# EVENTCTRL_FPGA.net
KiCad netlist of a schematic drawn in Altium Designer
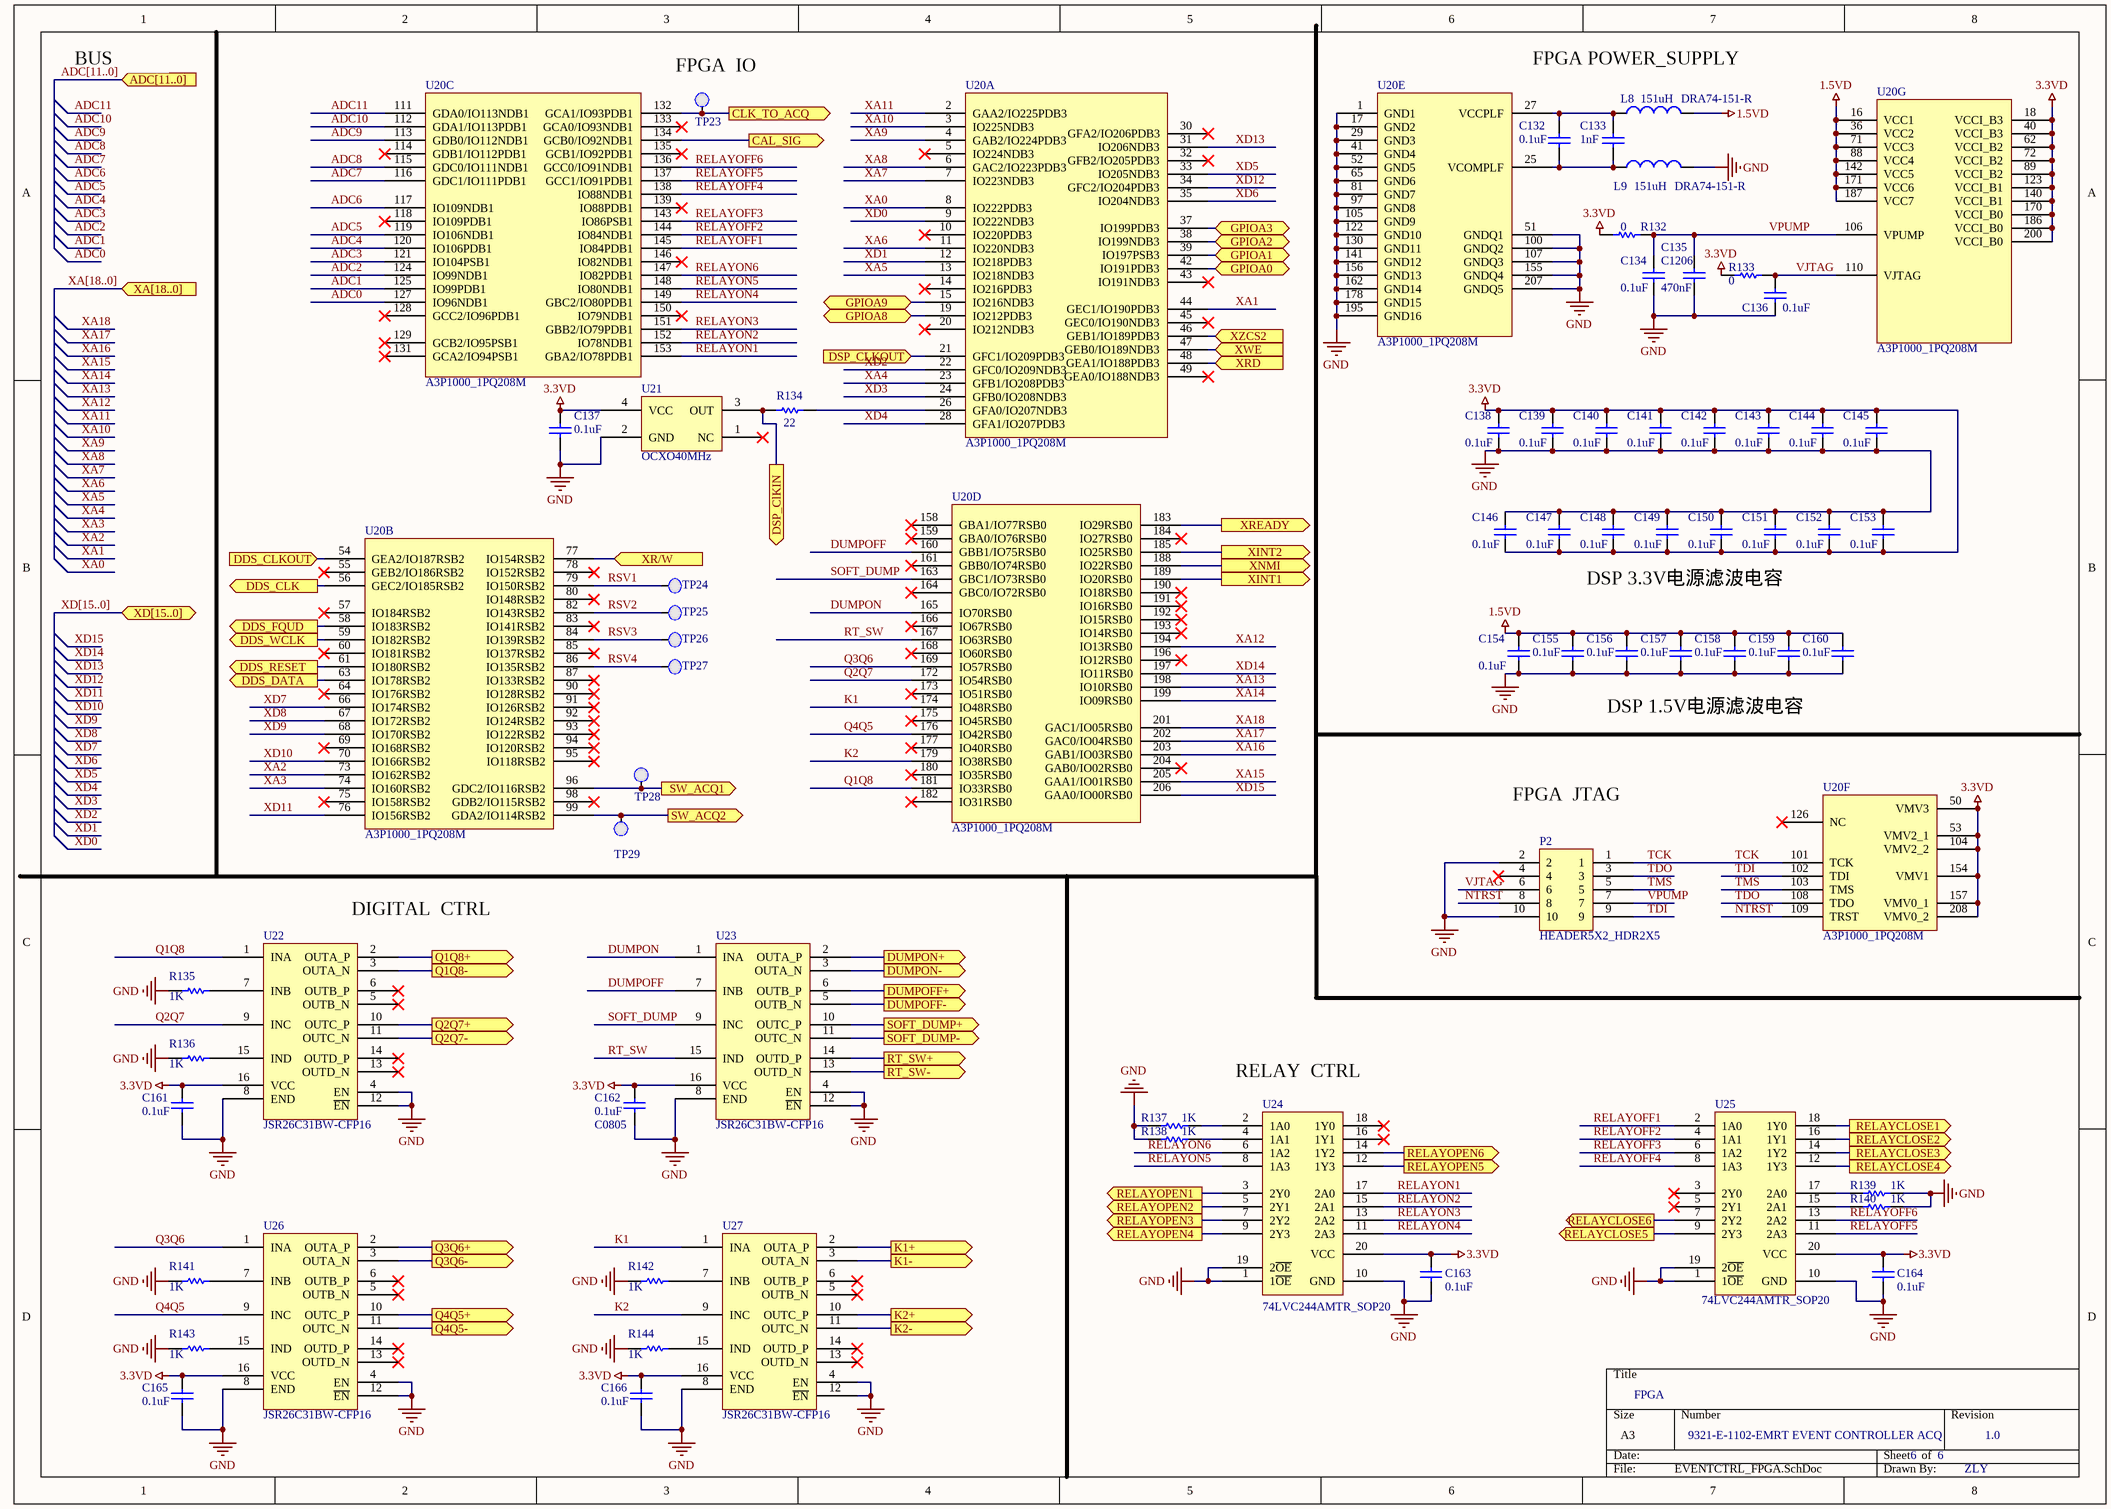
[diagram p0: EVENTCTRL_FPGA.SchDoc]

(export (version "E")
  (design (tool "Eeschema 10.0.6"))
  (components
    (comp (ref "C132")
      (value "0.1uF")
      (footprint "0805")
      (description "Capacitor")
      (fields (field (name "Comment") "C0805"))
      (libsource (lib "Miscellaneous Devices") (part "Cap"))
    )
    (comp (ref "C133")
      (value "1nF")
      (footprint "0805")
      (description "Capacitor")
      (fields (field (name "Comment") "C0805"))
      (libsource (lib "Miscellaneous Devices") (part "Cap"))
    )
    (comp (ref "C134")
      (value "0.1uF")
      (footprint "0805")
      (description "Capacitor")
      (fields (field (name "Comment") "C0805"))
      (libsource (lib "Miscellaneous Devices") (part "Cap"))
    )
    (comp (ref "C135")
      (value "C1206")
      (footprint "1206")
      (description "Capacitor")
      (fields (field (name "ALTIUM_VALUE") "470nF"))
      (libsource (lib "Miscellaneous Devices") (part "Cap"))
    )
    (comp (ref "C136")
      (value "0.1uF")
      (footprint "0805")
      (description "Capacitor")
      (fields (field (name "Comment") "C0805"))
      (libsource (lib "Miscellaneous Devices") (part "Cap"))
    )
    (comp (ref "C137")
      (value "0.1uF")
      (footprint "0805")
      (description "Capacitor")
      (fields (field (name "Comment") "C0805"))
      (libsource (lib "Miscellaneous Devices") (part "Cap"))
    )
    (comp (ref "C138")
      (value "0.1uF")
      (footprint "0805")
      (description "Capacitor")
      (fields (field (name "Comment") "C0805"))
      (libsource (lib "Miscellaneous Devices") (part "Cap"))
    )
    (comp (ref "C139")
      (value "0.1uF")
      (footprint "0805")
      (description "Capacitor")
      (fields (field (name "Comment") "C0805"))
      (libsource (lib "Miscellaneous Devices") (part "Cap"))
    )
    (comp (ref "C140")
      (value "0.1uF")
      (footprint "0805")
      (description "Capacitor")
      (fields (field (name "Comment") "C0805"))
      (libsource (lib "Miscellaneous Devices") (part "Cap"))
    )
    (comp (ref "C141")
      (value "0.1uF")
      (footprint "0805")
      (description "Capacitor")
      (fields (field (name "Comment") "C0805"))
      (libsource (lib "Miscellaneous Devices") (part "Cap"))
    )
    (comp (ref "C142")
      (value "0.1uF")
      (footprint "0805")
      (description "Capacitor")
      (fields (field (name "Comment") "C0805"))
      (libsource (lib "Miscellaneous Devices") (part "Cap"))
    )
    (comp (ref "C143")
      (value "0.1uF")
      (footprint "0805")
      (description "Capacitor")
      (fields (field (name "Comment") "C0805"))
      (libsource (lib "Miscellaneous Devices") (part "Cap"))
    )
    (comp (ref "C144")
      (value "0.1uF")
      (footprint "0805")
      (description "Capacitor")
      (fields (field (name "Comment") "C0805"))
      (libsource (lib "Miscellaneous Devices") (part "Cap"))
    )
    (comp (ref "C145")
      (value "0.1uF")
      (footprint "0805")
      (description "Capacitor")
      (fields (field (name "Comment") "C0805"))
      (libsource (lib "Miscellaneous Devices") (part "Cap"))
    )
    (comp (ref "C146")
      (value "0.1uF")
      (footprint "0805")
      (description "Capacitor")
      (fields (field (name "Comment") "C0805"))
      (libsource (lib "Miscellaneous Devices") (part "Cap"))
    )
    (comp (ref "C147")
      (value "0.1uF")
      (footprint "0805")
      (description "Capacitor")
      (fields (field (name "Comment") "C0805"))
      (libsource (lib "Miscellaneous Devices") (part "Cap"))
    )
    (comp (ref "C148")
      (value "0.1uF")
      (footprint "0805")
      (description "Capacitor")
      (fields (field (name "Comment") "C0805"))
      (libsource (lib "Miscellaneous Devices") (part "Cap"))
    )
    (comp (ref "C149")
      (value "0.1uF")
      (footprint "0805")
      (description "Capacitor")
      (fields (field (name "Comment") "C0805"))
      (libsource (lib "Miscellaneous Devices") (part "Cap"))
    )
    (comp (ref "C150")
      (value "0.1uF")
      (footprint "0805")
      (description "Capacitor")
      (fields (field (name "Comment") "C0805"))
      (libsource (lib "Miscellaneous Devices") (part "Cap"))
    )
    (comp (ref "C151")
      (value "0.1uF")
      (footprint "0805")
      (description "Capacitor")
      (fields (field (name "Comment") "C0805"))
      (libsource (lib "Miscellaneous Devices") (part "Cap"))
    )
    (comp (ref "C152")
      (value "0.1uF")
      (footprint "0805")
      (description "Capacitor")
      (fields (field (name "Comment") "C0805"))
      (libsource (lib "Miscellaneous Devices") (part "Cap"))
    )
    (comp (ref "C153")
      (value "0.1uF")
      (footprint "0805")
      (description "Capacitor")
      (fields (field (name "Comment") "C0805"))
      (libsource (lib "Miscellaneous Devices") (part "Cap"))
    )
    (comp (ref "C154")
      (value "0.1uF")
      (footprint "0805")
      (description "Capacitor")
      (fields (field (name "Comment") "C0805"))
      (libsource (lib "Miscellaneous Devices") (part "Cap"))
    )
    (comp (ref "C155")
      (value "0.1uF")
      (footprint "0805")
      (description "Capacitor")
      (fields (field (name "Comment") "C0805"))
      (libsource (lib "Miscellaneous Devices") (part "Cap"))
    )
    (comp (ref "C156")
      (value "0.1uF")
      (footprint "0805")
      (description "Capacitor")
      (fields (field (name "Comment") "C0805"))
      (libsource (lib "Miscellaneous Devices") (part "Cap"))
    )
    (comp (ref "C157")
      (value "0.1uF")
      (footprint "0805")
      (description "Capacitor")
      (fields (field (name "Comment") "C0805"))
      (libsource (lib "Miscellaneous Devices") (part "Cap"))
    )
    (comp (ref "C158")
      (value "0.1uF")
      (footprint "0805")
      (description "Capacitor")
      (fields (field (name "Comment") "C0805"))
      (libsource (lib "Miscellaneous Devices") (part "Cap"))
    )
    (comp (ref "C159")
      (value "0.1uF")
      (footprint "0805")
      (description "Capacitor")
      (fields (field (name "Comment") "C0805"))
      (libsource (lib "Miscellaneous Devices") (part "Cap"))
    )
    (comp (ref "C160")
      (value "0.1uF")
      (footprint "0805")
      (description "Capacitor")
      (fields (field (name "Comment") "C0805"))
      (libsource (lib "Miscellaneous Devices") (part "Cap"))
    )
    (comp (ref "C161")
      (value "0.1uF")
      (footprint "0805")
      (description "Capacitor")
      (fields (field (name "Comment") "C0805"))
      (libsource (lib "Miscellaneous Devices") (part "Cap"))
    )
    (comp (ref "C162")
      (value "0.1uF")
      (footprint "0805")
      (description "Capacitor")
      (fields (field (name "PACKAGEREFERENCE") "C0805") (field (name "Comment") "C0805"))
      (libsource (lib "Miscellaneous Devices") (part "Cap"))
    )
    (comp (ref "C163")
      (value "0.1uF")
      (footprint "0805")
      (description "Capacitor")
      (fields (field (name "Comment") "C0805"))
      (libsource (lib "Miscellaneous Devices") (part "Cap"))
    )
    (comp (ref "C164")
      (value "0.1uF")
      (footprint "0805")
      (description "Capacitor")
      (fields (field (name "Comment") "C0805"))
      (libsource (lib "Miscellaneous Devices") (part "Cap"))
    )
    (comp (ref "C165")
      (value "0.1uF")
      (footprint "0805")
      (description "Capacitor")
      (fields (field (name "Comment") "C0805"))
      (libsource (lib "Miscellaneous Devices") (part "Cap"))
    )
    (comp (ref "C166")
      (value "0.1uF")
      (footprint "0805")
      (description "Capacitor")
      (fields (field (name "Comment") "C0805"))
      (libsource (lib "Miscellaneous Devices") (part "Cap"))
    )
    (comp (ref "L8")
      (value "DRA74-151-R")
      (footprint "DRA74-151-R")
      (description "Inductor")
      (fields (field (name "ALTIUM_VALUE") "151uH"))
      (libsource (lib "Miscellaneous Devices") (part "Inductor"))
    )
    (comp (ref "L9")
      (value "DRA74-151-R")
      (footprint "DRA74-151-R")
      (description "Inductor")
      (fields (field (name "ALTIUM_VALUE") "151uH"))
      (libsource (lib "Miscellaneous Devices") (part "Inductor"))
    )
    (comp (ref "P2")
      (value "HEADER5X2_HDR2X5")
      (footprint "HDR2X5")
      (libsource (lib "srj") (part "JTAG_PORT10"))
    )
    (comp (ref "R132")
      (value "0")
      (footprint "R0805")
      (description "Resistor")
      (fields (field (name "Comment") "R0805"))
      (libsource (lib "Miscellaneous Devices") (part "Res1"))
    )
    (comp (ref "R133")
      (value "0")
      (footprint "R0805")
      (description "Resistor")
      (fields (field (name "Comment") "R0805"))
      (libsource (lib "Miscellaneous Devices") (part "Res1"))
    )
    (comp (ref "R134")
      (value "22")
      (footprint "R0805")
      (description "Resistor")
      (fields (field (name "Comment") "R0805"))
      (libsource (lib "Miscellaneous Devices") (part "Res1"))
    )
    (comp (ref "R135")
      (value "1K")
      (footprint "R0805")
      (description "Resistor")
      (fields (field (name "Comment") "R0805"))
      (libsource (lib "Miscellaneous Devices") (part "Res1"))
    )
    (comp (ref "R136")
      (value "1K")
      (footprint "R0805")
      (description "Resistor")
      (fields (field (name "Comment") "R0805"))
      (libsource (lib "Miscellaneous Devices") (part "Res1"))
    )
    (comp (ref "R137")
      (value "1K")
      (footprint "R0805")
      (description "Resistor")
      (fields (field (name "Comment") "R0805"))
      (libsource (lib "Miscellaneous Devices") (part "Res1"))
    )
    (comp (ref "R138")
      (value "1K")
      (footprint "R0805")
      (description "Resistor")
      (fields (field (name "Comment") "R0805"))
      (libsource (lib "Miscellaneous Devices") (part "Res1"))
    )
    (comp (ref "R139")
      (value "1K")
      (footprint "R0805")
      (description "Resistor")
      (fields (field (name "Comment") "R0805"))
      (libsource (lib "Miscellaneous Devices") (part "Res1"))
    )
    (comp (ref "R140")
      (value "1K")
      (footprint "R0805")
      (description "Resistor")
      (fields (field (name "Comment") "R0805"))
      (libsource (lib "Miscellaneous Devices") (part "Res1"))
    )
    (comp (ref "R141")
      (value "1K")
      (footprint "R0805")
      (description "Resistor")
      (fields (field (name "Comment") "R0805"))
      (libsource (lib "Miscellaneous Devices") (part "Res1"))
    )
    (comp (ref "R142")
      (value "1K")
      (footprint "R0805")
      (description "Resistor")
      (fields (field (name "Comment") "R0805"))
      (libsource (lib "Miscellaneous Devices") (part "Res1"))
    )
    (comp (ref "R143")
      (value "1K")
      (footprint "R0805")
      (description "Resistor")
      (fields (field (name "Comment") "R0805"))
      (libsource (lib "Miscellaneous Devices") (part "Res1"))
    )
    (comp (ref "R144")
      (value "1K")
      (footprint "R0805")
      (description "Resistor")
      (fields (field (name "Comment") "R0805"))
      (libsource (lib "Miscellaneous Devices") (part "Res1"))
    )
    (comp (ref "TP23") (value "TP") (footprint "TPA") (libsource (lib "") (part "TP_2")))
    (comp (ref "TP24") (value "TP") (footprint "TPA") (libsource (lib "*") (part "TP")))
    (comp (ref "TP25") (value "TP") (footprint "TPA") (libsource (lib "*") (part "TP")))
    (comp (ref "TP26") (value "TP") (footprint "TPA") (libsource (lib "*") (part "TP")))
    (comp (ref "TP27") (value "TP") (footprint "TPA") (libsource (lib "*") (part "TP")))
    (comp (ref "TP28") (value "TP") (footprint "TPA") (libsource (lib "") (part "TP_2")))
    (comp (ref "TP29") (value "TP") (footprint "TPA") (libsource (lib "") (part "TP_1")))
    (comp (ref "U20")
      (value "A3P1000_1PQ208M")
      (footprint "PQFP208")
      (libsource (lib "srj") (part "A3P1000"))
    )
    (comp (ref "U21") (value "OCXO40MHz") (footprint "OCX1") (libsource (lib "srj") (part "OCXO")))
    (comp (ref "U22") (value "JSR26C31BW-CFP16") (footprint "W16A") (libsource (lib "srj") (part "JSR26C31")))
    (comp (ref "U23") (value "JSR26C31BW-CFP16") (footprint "W16A") (libsource (lib "srj") (part "JSR26C31")))
    (comp (ref "U24")
      (value "74LVC244AMTR_SOP20")
      (footprint "EVENTCTRL:SOP20")
      (libsource (lib "srj") (part "74HC244"))
    )
    (comp (ref "U25")
      (value "74LVC244AMTR_SOP20")
      (footprint "EVENTCTRL:SOP20")
      (libsource (lib "srj") (part "74HC244"))
    )
    (comp (ref "U26") (value "JSR26C31BW-CFP16") (footprint "W16A") (libsource (lib "srj") (part "JSR26C31")))
    (comp (ref "U27") (value "JSR26C31BW-CFP16") (footprint "W16A") (libsource (lib "srj") (part "JSR26C31")))
  )
  (nets
    (net (code "1") (name "/ADC0") (class "Default")
      (node (ref "U20") (pin "127") (pinfunction "IO96NDB1_127") (pintype "passive"))
    )
    (net (code "2") (name "/ADC1") (class "Default")
      (node (ref "U20") (pin "125") (pinfunction "IO99PDB1_125") (pintype "passive"))
    )
    (net (code "3") (name "/ADC2") (class "Default")
      (node (ref "U20") (pin "124") (pinfunction "IO99NDB1_124") (pintype "passive"))
    )
    (net (code "4") (name "/ADC3") (class "Default")
      (node (ref "U20") (pin "121") (pinfunction "IO104PSB1_121") (pintype "passive"))
    )
    (net (code "5") (name "/ADC4") (class "Default")
      (node (ref "U20") (pin "120") (pinfunction "IO106PDB1_120") (pintype "passive"))
    )
    (net (code "6") (name "/ADC5") (class "Default")
      (node (ref "U20") (pin "119") (pinfunction "IO106NDB1_119") (pintype "passive"))
    )
    (net (code "7") (name "/ADC6") (class "Default")
      (node (ref "U20") (pin "117") (pinfunction "IO109NDB1_117") (pintype "passive"))
    )
    (net (code "8") (name "/ADC7") (class "Default")
      (node (ref "U20") (pin "116") (pinfunction "GDC1/IO111PDB1_116") (pintype "passive"))
    )
    (net (code "9") (name "/ADC8") (class "Default")
      (node (ref "U20") (pin "115") (pinfunction "GDC0/IO111NDB1_115") (pintype "passive"))
    )
    (net (code "10") (name "/ADC9") (class "Default")
      (node (ref "U20") (pin "113") (pinfunction "GDB0/IO112NDB1_113") (pintype "passive"))
    )
    (net (code "11") (name "/ADC10") (class "Default")
      (node (ref "U20") (pin "112") (pinfunction "GDA1/IO113PDB1_112") (pintype "passive"))
    )
    (net (code "12") (name "/ADC11") (class "Default")
      (node (ref "U20") (pin "111") (pinfunction "GDA0/IO113NDB1_111") (pintype "passive"))
    )
    (net (code "14") (name "/CAL_SIG") (class "Default")
      (node (ref "U20") (pin "134") (pinfunction "GCB0/IO92NDB1_134") (pintype "passive"))
    )
    (net (code "15") (name "/CLK_TO_ACQ") (class "Default")
      (node (ref "TP23") (pin "1") (pinfunction "TP_1") (pintype "passive"))
      (node (ref "U20") (pin "132") (pinfunction "GCA1/IO93PDB1_132") (pintype "passive"))
    )
    (net (code "16") (name "/DDS_CLK") (class "Default")
      (node (ref "U20") (pin "56") (pinfunction "GEC2/IO185RSB2_56") (pintype "passive"))
    )
    (net (code "17") (name "/DDS_CLKOUT") (class "Default")
      (node (ref "U20") (pin "54") (pinfunction "GEA2/IO187RSB2_54") (pintype "passive"))
    )
    (net (code "18") (name "/DDS_DATA") (class "Default")
      (node (ref "U20") (pin "63") (pinfunction "IO178RSB2_63") (pintype "passive"))
    )
    (net (code "19") (name "/DDS_FQUD") (class "Default")
      (node (ref "U20") (pin "58") (pinfunction "IO183RSB2_58") (pintype "passive"))
    )
    (net (code "20") (name "/DDS_RESET") (class "Default")
      (node (ref "U20") (pin "61") (pinfunction "IO180RSB2_61") (pintype "passive"))
    )
    (net (code "21") (name "/DDS_WCLK") (class "Default")
      (node (ref "U20") (pin "59") (pinfunction "IO182RSB2_59") (pintype "passive"))
    )
    (net (code "22") (name "/DSP_CLKOUT") (class "Default")
      (node (ref "U20") (pin "21") (pinfunction "GFC1/IO209PDB3_21") (pintype "passive"))
    )
    (net (code "23") (name "/DSP_ClKIN") (class "Default")
      (node (ref "R134") (pin "1") (pinfunction "1_1") (pintype "passive"))
      (node (ref "U21") (pin "3") (pinfunction "OUT_3") (pintype "passive"))
    )
    (net (code "24") (name "/DUMPOFF") (class "Default")
      (node (ref "U20") (pin "160") (pinfunction "GBB1/IO75RSB0_160") (pintype "passive"))
      (node (ref "U23") (pin "7") (pinfunction "INB_7") (pintype "passive"))
    )
    (net (code "25") (name "/DUMPOFF+") (class "Default")
      (node (ref "U23") (pin "6") (pinfunction "OUTB_P_6") (pintype "passive"))
    )
    (net (code "26") (name "/DUMPOFF-") (class "Default")
      (node (ref "U23") (pin "5") (pinfunction "OUTB_N_5") (pintype "passive"))
    )
    (net (code "27") (name "/DUMPON") (class "Default")
      (node (ref "U20") (pin "165") (pinfunction "IO70RSB0_165") (pintype "passive"))
      (node (ref "U23") (pin "1") (pinfunction "INA_1") (pintype "passive"))
    )
    (net (code "28") (name "/DUMPON+") (class "Default")
      (node (ref "U23") (pin "2") (pinfunction "OUTA_P_2") (pintype "passive"))
    )
    (net (code "29") (name "/DUMPON-") (class "Default")
      (node (ref "U23") (pin "3") (pinfunction "OUTA_N_3") (pintype "passive"))
    )
    (net (code "30") (name "/GPIOA0") (class "Default")
      (node (ref "U20") (pin "42") (pinfunction "IO191PDB3_42") (pintype "passive"))
    )
    (net (code "31") (name "/GPIOA1") (class "Default")
      (node (ref "U20") (pin "39") (pinfunction "IO197PSB3_39") (pintype "passive"))
    )
    (net (code "32") (name "/GPIOA2") (class "Default")
      (node (ref "U20") (pin "38") (pinfunction "IO199NDB3_38") (pintype "passive"))
    )
    (net (code "33") (name "/GPIOA3") (class "Default")
      (node (ref "U20") (pin "37") (pinfunction "IO199PDB3_37") (pintype "passive"))
    )
    (net (code "34") (name "/GPIOA8") (class "Default")
      (node (ref "U20") (pin "19") (pinfunction "IO212PDB3_19") (pintype "passive"))
    )
    (net (code "35") (name "/GPIOA9") (class "Default")
      (node (ref "U20") (pin "15") (pinfunction "IO216NDB3_15") (pintype "passive"))
    )
    (net (code "36") (name "/K1") (class "Default")
      (node (ref "U20") (pin "174") (pinfunction "IO48RSB0_174") (pintype "passive"))
      (node (ref "U27") (pin "1") (pinfunction "INA_1") (pintype "passive"))
    )
    (net (code "37") (name "/K1+") (class "Default")
      (node (ref "U27") (pin "2") (pinfunction "OUTA_P_2") (pintype "passive"))
    )
    (net (code "38") (name "/K1-") (class "Default")
      (node (ref "U27") (pin "3") (pinfunction "OUTA_N_3") (pintype "passive"))
    )
    (net (code "39") (name "/K2") (class "Default")
      (node (ref "U20") (pin "179") (pinfunction "IO38RSB0_179") (pintype "passive"))
      (node (ref "U27") (pin "9") (pinfunction "INC_9") (pintype "passive"))
    )
    (net (code "40") (name "/K2+") (class "Default")
      (node (ref "U27") (pin "10") (pinfunction "OUTC_P_10") (pintype "passive"))
    )
    (net (code "41") (name "/K2-") (class "Default")
      (node (ref "U27") (pin "11") (pinfunction "OUTC_N_11") (pintype "passive"))
    )
    (net (code "42") (name "/NTRST") (class "Default")
      (node (ref "P2") (pin "8") (pinfunction "8_8") (pintype "passive"))
      (node (ref "U20") (pin "109") (pinfunction "TRST_109") (pintype "passive"))
    )
    (net (code "43") (name "/Q1Q8") (class "Default")
      (node (ref "U20") (pin "181") (pinfunction "IO33RSB0_181") (pintype "passive"))
      (node (ref "U22") (pin "1") (pinfunction "INA_1") (pintype "passive"))
    )
    (net (code "44") (name "/Q1Q8+") (class "Default")
      (node (ref "U22") (pin "2") (pinfunction "OUTA_P_2") (pintype "passive"))
    )
    (net (code "45") (name "/Q1Q8-") (class "Default")
      (node (ref "U22") (pin "3") (pinfunction "OUTA_N_3") (pintype "passive"))
    )
    (net (code "46") (name "/Q2Q7") (class "Default")
      (node (ref "U20") (pin "172") (pinfunction "IO54RSB0_172") (pintype "passive"))
      (node (ref "U22") (pin "9") (pinfunction "INC_9") (pintype "passive"))
    )
    (net (code "47") (name "/Q2Q7+") (class "Default")
      (node (ref "U22") (pin "10") (pinfunction "OUTC_P_10") (pintype "passive"))
    )
    (net (code "48") (name "/Q2Q7-") (class "Default")
      (node (ref "U22") (pin "11") (pinfunction "OUTC_N_11") (pintype "passive"))
    )
    (net (code "49") (name "/Q3Q6") (class "Default")
      (node (ref "U20") (pin "169") (pinfunction "IO57RSB0_169") (pintype "passive"))
      (node (ref "U26") (pin "1") (pinfunction "INA_1") (pintype "passive"))
    )
    (net (code "50") (name "/Q3Q6+") (class "Default")
      (node (ref "U26") (pin "2") (pinfunction "OUTA_P_2") (pintype "passive"))
    )
    (net (code "51") (name "/Q3Q6-") (class "Default")
      (node (ref "U26") (pin "3") (pinfunction "OUTA_N_3") (pintype "passive"))
    )
    (net (code "52") (name "/Q4Q5") (class "Default")
      (node (ref "U20") (pin "176") (pinfunction "IO42RSB0_176") (pintype "passive"))
      (node (ref "U26") (pin "9") (pinfunction "INC_9") (pintype "passive"))
    )
    (net (code "53") (name "/Q4Q5+") (class "Default")
      (node (ref "U26") (pin "10") (pinfunction "OUTC_P_10") (pintype "passive"))
    )
    (net (code "54") (name "/Q4Q5-") (class "Default")
      (node (ref "U26") (pin "11") (pinfunction "OUTC_N_11") (pintype "passive"))
    )
    (net (code "55") (name "/RELAYCLOSE1") (class "Default")
      (node (ref "U25") (pin "18") (pinfunction "1Y0_18") (pintype "passive"))
    )
    (net (code "56") (name "/RELAYCLOSE2") (class "Default")
      (node (ref "U25") (pin "16") (pinfunction "1Y1_16") (pintype "passive"))
    )
    (net (code "57") (name "/RELAYCLOSE3") (class "Default")
      (node (ref "U25") (pin "14") (pinfunction "1Y2_14") (pintype "passive"))
    )
    (net (code "58") (name "/RELAYCLOSE4") (class "Default")
      (node (ref "U25") (pin "12") (pinfunction "1Y3_12") (pintype "passive"))
    )
    (net (code "59") (name "/RELAYCLOSE5") (class "Default")
      (node (ref "U25") (pin "9") (pinfunction "2Y3_9") (pintype "passive"))
    )
    (net (code "60") (name "/RELAYCLOSE6") (class "Default")
      (node (ref "U25") (pin "7") (pinfunction "2Y2_7") (pintype "passive"))
    )
    (net (code "61") (name "/RELAYOFF1") (class "Default")
      (node (ref "U20") (pin "145") (pinfunction "IO84PDB1_145") (pintype "passive"))
      (node (ref "U25") (pin "2") (pinfunction "1A0_2") (pintype "passive"))
    )
    (net (code "62") (name "/RELAYOFF2") (class "Default")
      (node (ref "U20") (pin "144") (pinfunction "IO84NDB1_144") (pintype "passive"))
      (node (ref "U25") (pin "4") (pinfunction "1A1_4") (pintype "passive"))
    )
    (net (code "63") (name "/RELAYOFF3") (class "Default")
      (node (ref "U20") (pin "143") (pinfunction "IO86PSB1_143") (pintype "passive"))
      (node (ref "U25") (pin "6") (pinfunction "1A2_6") (pintype "passive"))
    )
    (net (code "64") (name "/RELAYOFF4") (class "Default")
      (node (ref "U20") (pin "138") (pinfunction "IO88NDB1_138") (pintype "passive"))
      (node (ref "U25") (pin "8") (pinfunction "1A3_8") (pintype "passive"))
    )
    (net (code "65") (name "/RELAYOFF5") (class "Default")
      (node (ref "U20") (pin "137") (pinfunction "GCC1/IO91PDB1_137") (pintype "passive"))
      (node (ref "U25") (pin "11") (pinfunction "2A3_11") (pintype "passive"))
    )
    (net (code "66") (name "/RELAYOFF6") (class "Default")
      (node (ref "U20") (pin "136") (pinfunction "GCC0/IO91NDB1_136") (pintype "passive"))
      (node (ref "U25") (pin "13") (pinfunction "2A2_13") (pintype "passive"))
    )
    (net (code "67") (name "/RELAYON1") (class "Default")
      (node (ref "U20") (pin "153") (pinfunction "GBA2/IO78PDB1_153") (pintype "passive"))
      (node (ref "U24") (pin "17") (pinfunction "2A0_17") (pintype "passive"))
    )
    (net (code "68") (name "/RELAYON2") (class "Default")
      (node (ref "U20") (pin "152") (pinfunction "IO78NDB1_152") (pintype "passive"))
      (node (ref "U24") (pin "15") (pinfunction "2A1_15") (pintype "passive"))
    )
    (net (code "69") (name "/RELAYON3") (class "Default")
      (node (ref "U20") (pin "151") (pinfunction "GBB2/IO79PDB1_151") (pintype "passive"))
      (node (ref "U24") (pin "13") (pinfunction "2A2_13") (pintype "passive"))
    )
    (net (code "70") (name "/RELAYON4") (class "Default")
      (node (ref "U20") (pin "149") (pinfunction "GBC2/IO80PDB1_149") (pintype "passive"))
      (node (ref "U24") (pin "11") (pinfunction "2A3_11") (pintype "passive"))
    )
    (net (code "71") (name "/RELAYON5") (class "Default")
      (node (ref "U20") (pin "148") (pinfunction "IO80NDB1_148") (pintype "passive"))
      (node (ref "U24") (pin "8") (pinfunction "1A3_8") (pintype "passive"))
    )
    (net (code "72") (name "/RELAYON6") (class "Default")
      (node (ref "U20") (pin "147") (pinfunction "IO82PDB1_147") (pintype "passive"))
      (node (ref "U24") (pin "6") (pinfunction "1A2_6") (pintype "passive"))
    )
    (net (code "73") (name "/RELAYOPEN1") (class "Default")
      (node (ref "U24") (pin "3") (pinfunction "2Y0_3") (pintype "passive"))
    )
    (net (code "74") (name "/RELAYOPEN2") (class "Default")
      (node (ref "U24") (pin "5") (pinfunction "2Y1_5") (pintype "passive"))
    )
    (net (code "75") (name "/RELAYOPEN3") (class "Default")
      (node (ref "U24") (pin "7") (pinfunction "2Y2_7") (pintype "passive"))
    )
    (net (code "76") (name "/RELAYOPEN4") (class "Default")
      (node (ref "U24") (pin "9") (pinfunction "2Y3_9") (pintype "passive"))
    )
    (net (code "77") (name "/RELAYOPEN5") (class "Default")
      (node (ref "U24") (pin "12") (pinfunction "1Y3_12") (pintype "passive"))
    )
    (net (code "78") (name "/RELAYOPEN6") (class "Default")
      (node (ref "U24") (pin "14") (pinfunction "1Y2_14") (pintype "passive"))
    )
    (net (code "79") (name "/RSV1") (class "Default")
      (node (ref "TP24") (pin "1") (pinfunction "TP_1") (pintype "passive"))
      (node (ref "U20") (pin "79") (pinfunction "IO150RSB2_79") (pintype "passive"))
    )
    (net (code "80") (name "/RSV2") (class "Default")
      (node (ref "TP25") (pin "1") (pinfunction "TP_1") (pintype "passive"))
      (node (ref "U20") (pin "82") (pinfunction "IO143RSB2_82") (pintype "passive"))
    )
    (net (code "81") (name "/RSV3") (class "Default")
      (node (ref "TP26") (pin "1") (pinfunction "TP_1") (pintype "passive"))
      (node (ref "U20") (pin "84") (pinfunction "IO139RSB2_84") (pintype "passive"))
    )
    (net (code "82") (name "/RSV4") (class "Default")
      (node (ref "TP27") (pin "1") (pinfunction "TP_1") (pintype "passive"))
      (node (ref "U20") (pin "86") (pinfunction "IO135RSB2_86") (pintype "passive"))
    )
    (net (code "83") (name "/RT_SW") (class "Default")
      (node (ref "U20") (pin "167") (pinfunction "IO63RSB0_167") (pintype "passive"))
      (node (ref "U23") (pin "15") (pinfunction "IND_15") (pintype "passive"))
    )
    (net (code "84") (name "/RT_SW+") (class "Default")
      (node (ref "U23") (pin "14") (pinfunction "OUTD_P_14") (pintype "passive"))
    )
    (net (code "85") (name "/RT_SW-") (class "Default")
      (node (ref "U23") (pin "13") (pinfunction "OUTD_N_13") (pintype "passive"))
    )
    (net (code "86") (name "/SOFT_DUMP") (class "Default")
      (node (ref "U20") (pin "163") (pinfunction "GBC1/IO73RSB0_163") (pintype "passive"))
      (node (ref "U23") (pin "9") (pinfunction "INC_9") (pintype "passive"))
    )
    (net (code "87") (name "/SOFT_DUMP+") (class "Default")
      (node (ref "U23") (pin "10") (pinfunction "OUTC_P_10") (pintype "passive"))
    )
    (net (code "88") (name "/SOFT_DUMP-") (class "Default")
      (node (ref "U23") (pin "11") (pinfunction "OUTC_N_11") (pintype "passive"))
    )
    (net (code "89") (name "/SW_ACQ1") (class "Default")
      (node (ref "TP28") (pin "1") (pinfunction "TP_1") (pintype "passive"))
      (node (ref "U20") (pin "96") (pinfunction "GDC2/IO116RSB2_96") (pintype "passive"))
    )
    (net (code "90") (name "/SW_ACQ2") (class "Default")
      (node (ref "TP29") (pin "1") (pinfunction "TP_1") (pintype "passive"))
      (node (ref "U20") (pin "99") (pinfunction "GDA2/IO114RSB2_99") (pintype "passive"))
    )
    (net (code "91") (name "/TCK") (class "Default")
      (node (ref "P2") (pin "1") (pinfunction "1_1") (pintype "passive"))
      (node (ref "U20") (pin "101") (pinfunction "TCK_101") (pintype "passive"))
    )
    (net (code "92") (name "/TDI") (class "Default")
      (node (ref "P2") (pin "9") (pinfunction "9_9") (pintype "passive"))
      (node (ref "U20") (pin "102") (pinfunction "TDI_102") (pintype "passive"))
    )
    (net (code "93") (name "/TDO") (class "Default")
      (node (ref "P2") (pin "3") (pinfunction "3_3") (pintype "passive"))
      (node (ref "U20") (pin "108") (pinfunction "TDO_108") (pintype "passive"))
    )
    (net (code "94") (name "/TMS") (class "Default")
      (node (ref "P2") (pin "5") (pinfunction "5_5") (pintype "passive"))
      (node (ref "U20") (pin "103") (pinfunction "TMS_103") (pintype "passive"))
    )
    (net (code "95") (name "/VJTAG") (class "Default")
      (node (ref "C136") (pin "1") (pinfunction "1_1") (pintype "passive"))
      (node (ref "P2") (pin "6") (pinfunction "6_6") (pintype "passive"))
      (node (ref "R133") (pin "2") (pinfunction "2_2") (pintype "passive"))
      (node (ref "U20") (pin "110") (pinfunction "VJTAG_110") (pintype "passive"))
    )
    (net (code "96") (name "/VPUMP") (class "Default")
      (node (ref "C134") (pin "1") (pinfunction "1_1") (pintype "passive"))
      (node (ref "C135") (pin "1") (pinfunction "1_1") (pintype "passive"))
      (node (ref "P2") (pin "7") (pinfunction "7_7") (pintype "passive"))
      (node (ref "R132") (pin "2") (pinfunction "2_2") (pintype "passive"))
      (node (ref "U20") (pin "106") (pinfunction "VPUMP_106") (pintype "passive"))
    )
    (net (code "97") (name "/XA0") (class "Default")
      (node (ref "U20") (pin "8") (pinfunction "IO222PDB3_8") (pintype "passive"))
    )
    (net (code "98") (name "/XA1") (class "Default")
      (node (ref "U20") (pin "44") (pinfunction "GEC1/IO190PDB3_44") (pintype "passive"))
    )
    (net (code "99") (name "/XA2") (class "Default")
      (node (ref "U20") (pin "73") (pinfunction "IO162RSB2_73") (pintype "passive"))
    )
    (net (code "100") (name "/XA3") (class "Default")
      (node (ref "U20") (pin "74") (pinfunction "IO160RSB2_74") (pintype "passive"))
    )
    (net (code "101") (name "/XA4") (class "Default")
      (node (ref "U20") (pin "23") (pinfunction "GFB1/IO208PDB3_23") (pintype "passive"))
    )
    (net (code "102") (name "/XA5") (class "Default")
      (node (ref "U20") (pin "13") (pinfunction "IO218NDB3_13") (pintype "passive"))
    )
    (net (code "103") (name "/XA6") (class "Default")
      (node (ref "U20") (pin "11") (pinfunction "IO220NDB3_11") (pintype "passive"))
    )
    (net (code "104") (name "/XA7") (class "Default")
      (node (ref "U20") (pin "7") (pinfunction "IO223NDB3_7") (pintype "passive"))
    )
    (net (code "105") (name "/XA8") (class "Default")
      (node (ref "U20") (pin "6") (pinfunction "GAC2/IO223PDB3_6") (pintype "passive"))
    )
    (net (code "106") (name "/XA9") (class "Default")
      (node (ref "U20") (pin "4") (pinfunction "GAB2/IO224PDB3_4") (pintype "passive"))
    )
    (net (code "107") (name "/XA10") (class "Default")
      (node (ref "U20") (pin "3") (pinfunction "IO225NDB3_3") (pintype "passive"))
    )
    (net (code "108") (name "/XA11") (class "Default")
      (node (ref "U20") (pin "2") (pinfunction "GAA2/IO225PDB3_2") (pintype "passive"))
    )
    (net (code "109") (name "/XA12") (class "Default")
      (node (ref "U20") (pin "194") (pinfunction "IO13RSB0_194") (pintype "passive"))
    )
    (net (code "110") (name "/XA13") (class "Default")
      (node (ref "U20") (pin "198") (pinfunction "IO10RSB0_198") (pintype "passive"))
    )
    (net (code "111") (name "/XA14") (class "Default")
      (node (ref "U20") (pin "199") (pinfunction "IO09RSB0_199") (pintype "passive"))
    )
    (net (code "112") (name "/XA15") (class "Default")
      (node (ref "U20") (pin "205") (pinfunction "GAA1/IO01RSB0_205") (pintype "passive"))
    )
    (net (code "113") (name "/XA16") (class "Default")
      (node (ref "U20") (pin "203") (pinfunction "GAB1/IO03RSB0_203") (pintype "passive"))
    )
    (net (code "114") (name "/XA17") (class "Default")
      (node (ref "U20") (pin "202") (pinfunction "GAC0/IO04RSB0_202") (pintype "passive"))
    )
    (net (code "115") (name "/XA18") (class "Default")
      (node (ref "U20") (pin "201") (pinfunction "GAC1/IO05RSB0_201") (pintype "passive"))
    )
    (net (code "117") (name "/XD0") (class "Default")
      (node (ref "U20") (pin "9") (pinfunction "IO222NDB3_9") (pintype "passive"))
    )
    (net (code "118") (name "/XD1") (class "Default")
      (node (ref "U20") (pin "12") (pinfunction "IO218PDB3_12") (pintype "passive"))
    )
    (net (code "119") (name "/XD2") (class "Default")
      (node (ref "U20") (pin "22") (pinfunction "GFC0/IO209NDB3_22") (pintype "passive"))
    )
    (net (code "120") (name "/XD3") (class "Default")
      (node (ref "U20") (pin "24") (pinfunction "GFB0/IO208NDB3_24") (pintype "passive"))
    )
    (net (code "121") (name "/XD4") (class "Default")
      (node (ref "U20") (pin "28") (pinfunction "GFA1/IO207PDB3_28") (pintype "passive"))
    )
    (net (code "122") (name "/XD5") (class "Default")
      (node (ref "U20") (pin "33") (pinfunction "IO205NDB3_33") (pintype "passive"))
    )
    (net (code "123") (name "/XD6") (class "Default")
      (node (ref "U20") (pin "35") (pinfunction "IO204NDB3_35") (pintype "passive"))
    )
    (net (code "124") (name "/XD7") (class "Default")
      (node (ref "U20") (pin "66") (pinfunction "IO174RSB2_66") (pintype "passive"))
    )
    (net (code "125") (name "/XD8") (class "Default")
      (node (ref "U20") (pin "67") (pinfunction "IO172RSB2_67") (pintype "passive"))
    )
    (net (code "126") (name "/XD9") (class "Default")
      (node (ref "U20") (pin "68") (pinfunction "IO170RSB2_68") (pintype "passive"))
    )
    (net (code "127") (name "/XD10") (class "Default")
      (node (ref "U20") (pin "70") (pinfunction "IO166RSB2_70") (pintype "passive"))
    )
    (net (code "128") (name "/XD11") (class "Default")
      (node (ref "U20") (pin "76") (pinfunction "IO156RSB2_76") (pintype "passive"))
    )
    (net (code "129") (name "/XD12") (class "Default")
      (node (ref "U20") (pin "34") (pinfunction "GFC2/IO204PDB3_34") (pintype "passive"))
    )
    (net (code "130") (name "/XD13") (class "Default")
      (node (ref "U20") (pin "31") (pinfunction "IO206NDB3_31") (pintype "passive"))
    )
    (net (code "131") (name "/XD14") (class "Default")
      (node (ref "U20") (pin "197") (pinfunction "IO11RSB0_197") (pintype "passive"))
    )
    (net (code "132") (name "/XD15") (class "Default")
      (node (ref "U20") (pin "206") (pinfunction "GAA0/IO00RSB0_206") (pintype "passive"))
    )
    (net (code "134") (name "/XINT1") (class "Default")
      (node (ref "U20") (pin "189") (pinfunction "IO20RSB0_189") (pintype "passive"))
    )
    (net (code "135") (name "/XINT2") (class "Default")
      (node (ref "U20") (pin "185") (pinfunction "IO25RSB0_185") (pintype "passive"))
    )
    (net (code "136") (name "/XNMI") (class "Default")
      (node (ref "U20") (pin "188") (pinfunction "IO22RSB0_188") (pintype "passive"))
    )
    (net (code "137") (name "/XRD") (class "Default")
      (node (ref "U20") (pin "48") (pinfunction "GEA1/IO188PDB3_48") (pintype "passive"))
    )
    (net (code "138") (name "/XREADY") (class "Default")
      (node (ref "U20") (pin "183") (pinfunction "IO29RSB0_183") (pintype "passive"))
    )
    (net (code "139") (name "/XR{slash}W") (class "Default")
      (node (ref "U20") (pin "77") (pinfunction "IO154RSB2_77") (pintype "passive"))
    )
    (net (code "140") (name "/XWE") (class "Default")
      (node (ref "U20") (pin "47") (pinfunction "GEB0/IO189NDB3_47") (pintype "passive"))
    )
    (net (code "141") (name "/XZCS2") (class "Default")
      (node (ref "U20") (pin "46") (pinfunction "GEB1/IO189PDB3_46") (pintype "passive"))
    )
    (net (code "142") (name "1.5VD") (class "Default")
      (node (ref "C154") (pin "1") (pinfunction "1_1") (pintype "passive"))
      (node (ref "C155") (pin "1") (pinfunction "1_1") (pintype "passive"))
      (node (ref "C156") (pin "1") (pinfunction "1_1") (pintype "passive"))
      (node (ref "C157") (pin "1") (pinfunction "1_1") (pintype "passive"))
      (node (ref "C158") (pin "1") (pinfunction "1_1") (pintype "passive"))
      (node (ref "C159") (pin "1") (pinfunction "1_1") (pintype "passive"))
      (node (ref "C160") (pin "1") (pinfunction "1_1") (pintype "passive"))
      (node (ref "L8") (pin "2") (pinfunction "2_2") (pintype "passive"))
      (node (ref "U20") (pin "142") (pinfunction "VCC5_142") (pintype "passive"))
      (node (ref "U20") (pin "16") (pinfunction "VCC1_16") (pintype "passive"))
      (node (ref "U20") (pin "171") (pinfunction "VCC6_171") (pintype "passive"))
      (node (ref "U20") (pin "187") (pinfunction "VCC7_187") (pintype "passive"))
      (node (ref "U20") (pin "36") (pinfunction "VCC2_36") (pintype "passive"))
      (node (ref "U20") (pin "71") (pinfunction "VCC3_71") (pintype "passive"))
      (node (ref "U20") (pin "88") (pinfunction "VCC4_88") (pintype "passive"))
    )
    (net (code "143") (name "3.3VD") (class "Default")
      (node (ref "C137") (pin "1") (pinfunction "1_1") (pintype "passive"))
      (node (ref "C138") (pin "1") (pinfunction "1_1") (pintype "passive"))
      (node (ref "C139") (pin "1") (pinfunction "1_1") (pintype "passive"))
      (node (ref "C140") (pin "1") (pinfunction "1_1") (pintype "passive"))
      (node (ref "C141") (pin "1") (pinfunction "1_1") (pintype "passive"))
      (node (ref "C142") (pin "1") (pinfunction "1_1") (pintype "passive"))
      (node (ref "C143") (pin "1") (pinfunction "1_1") (pintype "passive"))
      (node (ref "C144") (pin "1") (pinfunction "1_1") (pintype "passive"))
      (node (ref "C145") (pin "1") (pinfunction "1_1") (pintype "passive"))
      (node (ref "C146") (pin "2") (pinfunction "2_2") (pintype "passive"))
      (node (ref "C147") (pin "2") (pinfunction "2_2") (pintype "passive"))
      (node (ref "C148") (pin "2") (pinfunction "2_2") (pintype "passive"))
      (node (ref "C149") (pin "2") (pinfunction "2_2") (pintype "passive"))
      (node (ref "C150") (pin "2") (pinfunction "2_2") (pintype "passive"))
      (node (ref "C151") (pin "2") (pinfunction "2_2") (pintype "passive"))
      (node (ref "C152") (pin "2") (pinfunction "2_2") (pintype "passive"))
      (node (ref "C153") (pin "2") (pinfunction "2_2") (pintype "passive"))
      (node (ref "C161") (pin "1") (pinfunction "1_1") (pintype "passive"))
      (node (ref "C162") (pin "1") (pinfunction "1_1") (pintype "passive"))
      (node (ref "C163") (pin "2") (pinfunction "2_2") (pintype "passive"))
      (node (ref "C164") (pin "2") (pinfunction "2_2") (pintype "passive"))
      (node (ref "C165") (pin "1") (pinfunction "1_1") (pintype "passive"))
      (node (ref "C166") (pin "1") (pinfunction "1_1") (pintype "passive"))
      (node (ref "R132") (pin "1") (pinfunction "1_1") (pintype "passive"))
      (node (ref "R133") (pin "1") (pinfunction "1_1") (pintype "passive"))
      (node (ref "U20") (pin "104") (pinfunction "VMV2_2_104") (pintype "passive"))
      (node (ref "U20") (pin "123") (pinfunction "VCCI_B1_123") (pintype "passive"))
      (node (ref "U20") (pin "140") (pinfunction "VCCI_B1_140") (pintype "passive"))
      (node (ref "U20") (pin "154") (pinfunction "VMV1_154") (pintype "passive"))
      (node (ref "U20") (pin "157") (pinfunction "VMV0_1_157") (pintype "passive"))
      (node (ref "U20") (pin "170") (pinfunction "VCCI_B0_170") (pintype "passive"))
      (node (ref "U20") (pin "18") (pinfunction "VCCI_B3_18") (pintype "passive"))
      (node (ref "U20") (pin "186") (pinfunction "VCCI_B0_186") (pintype "passive"))
      (node (ref "U20") (pin "200") (pinfunction "VCCI_B0_200") (pintype "passive"))
      (node (ref "U20") (pin "208") (pinfunction "VMV0_2_208") (pintype "passive"))
      (node (ref "U20") (pin "40") (pinfunction "VCCI_B3_40") (pintype "passive"))
      (node (ref "U20") (pin "50") (pinfunction "VMV3_50") (pintype "passive"))
      (node (ref "U20") (pin "53") (pinfunction "VMV2_1_53") (pintype "passive"))
      (node (ref "U20") (pin "62") (pinfunction "VCCI_B2_62") (pintype "passive"))
      (node (ref "U20") (pin "72") (pinfunction "VCCI_B2_72") (pintype "passive"))
      (node (ref "U20") (pin "89") (pinfunction "VCCI_B2_89") (pintype "passive"))
      (node (ref "U21") (pin "4") (pinfunction "VCC_4") (pintype "passive"))
      (node (ref "U22") (pin "16") (pinfunction "VCC_16") (pintype "passive"))
      (node (ref "U23") (pin "16") (pinfunction "VCC_16") (pintype "passive"))
      (node (ref "U24") (pin "20") (pinfunction "VCC_20") (pintype "passive"))
      (node (ref "U25") (pin "20") (pinfunction "VCC_20") (pintype "passive"))
      (node (ref "U26") (pin "16") (pinfunction "VCC_16") (pintype "passive"))
      (node (ref "U27") (pin "16") (pinfunction "VCC_16") (pintype "passive"))
    )
    (net (code "144") (name "GND") (class "Default")
      (node (ref "C134") (pin "2") (pinfunction "2_2") (pintype "passive"))
      (node (ref "C135") (pin "2") (pinfunction "2_2") (pintype "passive"))
      (node (ref "C136") (pin "2") (pinfunction "2_2") (pintype "passive"))
      (node (ref "C137") (pin "2") (pinfunction "2_2") (pintype "passive"))
      (node (ref "C138") (pin "2") (pinfunction "2_2") (pintype "passive"))
      (node (ref "C139") (pin "2") (pinfunction "2_2") (pintype "passive"))
      (node (ref "C140") (pin "2") (pinfunction "2_2") (pintype "passive"))
      (node (ref "C141") (pin "2") (pinfunction "2_2") (pintype "passive"))
      (node (ref "C142") (pin "2") (pinfunction "2_2") (pintype "passive"))
      (node (ref "C143") (pin "2") (pinfunction "2_2") (pintype "passive"))
      (node (ref "C144") (pin "2") (pinfunction "2_2") (pintype "passive"))
      (node (ref "C145") (pin "2") (pinfunction "2_2") (pintype "passive"))
      (node (ref "C146") (pin "1") (pinfunction "1_1") (pintype "passive"))
      (node (ref "C147") (pin "1") (pinfunction "1_1") (pintype "passive"))
      (node (ref "C148") (pin "1") (pinfunction "1_1") (pintype "passive"))
      (node (ref "C149") (pin "1") (pinfunction "1_1") (pintype "passive"))
      (node (ref "C150") (pin "1") (pinfunction "1_1") (pintype "passive"))
      (node (ref "C151") (pin "1") (pinfunction "1_1") (pintype "passive"))
      (node (ref "C152") (pin "1") (pinfunction "1_1") (pintype "passive"))
      (node (ref "C153") (pin "1") (pinfunction "1_1") (pintype "passive"))
      (node (ref "C154") (pin "2") (pinfunction "2_2") (pintype "passive"))
      (node (ref "C155") (pin "2") (pinfunction "2_2") (pintype "passive"))
      (node (ref "C156") (pin "2") (pinfunction "2_2") (pintype "passive"))
      (node (ref "C157") (pin "2") (pinfunction "2_2") (pintype "passive"))
      (node (ref "C158") (pin "2") (pinfunction "2_2") (pintype "passive"))
      (node (ref "C159") (pin "2") (pinfunction "2_2") (pintype "passive"))
      (node (ref "C160") (pin "2") (pinfunction "2_2") (pintype "passive"))
      (node (ref "C161") (pin "2") (pinfunction "2_2") (pintype "passive"))
      (node (ref "C162") (pin "2") (pinfunction "2_2") (pintype "passive"))
      (node (ref "C163") (pin "1") (pinfunction "1_1") (pintype "passive"))
      (node (ref "C164") (pin "1") (pinfunction "1_1") (pintype "passive"))
      (node (ref "C165") (pin "2") (pinfunction "2_2") (pintype "passive"))
      (node (ref "C166") (pin "2") (pinfunction "2_2") (pintype "passive"))
      (node (ref "L9") (pin "2") (pinfunction "2_2") (pintype "passive"))
      (node (ref "P2") (pin "10") (pinfunction "10_10") (pintype "passive"))
      (node (ref "P2") (pin "2") (pinfunction "2_2") (pintype "passive"))
      (node (ref "R135") (pin "1") (pinfunction "1_1") (pintype "passive"))
      (node (ref "R136") (pin "1") (pinfunction "1_1") (pintype "passive"))
      (node (ref "R137") (pin "1") (pinfunction "1_1") (pintype "passive"))
      (node (ref "R138") (pin "1") (pinfunction "1_1") (pintype "passive"))
      (node (ref "R139") (pin "2") (pinfunction "2_2") (pintype "passive"))
      (node (ref "R140") (pin "2") (pinfunction "2_2") (pintype "passive"))
      (node (ref "R141") (pin "1") (pinfunction "1_1") (pintype "passive"))
      (node (ref "R142") (pin "1") (pinfunction "1_1") (pintype "passive"))
      (node (ref "R143") (pin "1") (pinfunction "1_1") (pintype "passive"))
      (node (ref "R144") (pin "1") (pinfunction "1_1") (pintype "passive"))
      (node (ref "U20") (pin "1") (pinfunction "GND1_1") (pintype "passive"))
      (node (ref "U20") (pin "100") (pinfunction "GNDQ2_100") (pintype "passive"))
      (node (ref "U20") (pin "105") (pinfunction "GND9_105") (pintype "passive"))
      (node (ref "U20") (pin "107") (pinfunction "GNDQ3_107") (pintype "passive"))
      (node (ref "U20") (pin "122") (pinfunction "GND10_122") (pintype "passive"))
      (node (ref "U20") (pin "130") (pinfunction "GND11_130") (pintype "passive"))
      (node (ref "U20") (pin "141") (pinfunction "GND12_141") (pintype "passive"))
      (node (ref "U20") (pin "155") (pinfunction "GNDQ4_155") (pintype "passive"))
      (node (ref "U20") (pin "156") (pinfunction "GND13_156") (pintype "passive"))
      (node (ref "U20") (pin "162") (pinfunction "GND14_162") (pintype "passive"))
      (node (ref "U20") (pin "17") (pinfunction "GND2_17") (pintype "passive"))
      (node (ref "U20") (pin "178") (pinfunction "GND15_178") (pintype "passive"))
      (node (ref "U20") (pin "195") (pinfunction "GND16_195") (pintype "passive"))
      (node (ref "U20") (pin "207") (pinfunction "GNDQ5_207") (pintype "passive"))
      (node (ref "U20") (pin "29") (pinfunction "GND3_29") (pintype "passive"))
      (node (ref "U20") (pin "41") (pinfunction "GND4_41") (pintype "passive"))
      (node (ref "U20") (pin "51") (pinfunction "GNDQ1_51") (pintype "passive"))
      (node (ref "U20") (pin "52") (pinfunction "GND5_52") (pintype "passive"))
      (node (ref "U20") (pin "65") (pinfunction "GND6_65") (pintype "passive"))
      (node (ref "U20") (pin "81") (pinfunction "GND7_81") (pintype "passive"))
      (node (ref "U20") (pin "97") (pinfunction "GND8_97") (pintype "passive"))
      (node (ref "U21") (pin "2") (pinfunction "GND_2") (pintype "passive"))
      (node (ref "U22") (pin "12") (pinfunction "~{EN}_12") (pintype "passive"))
      (node (ref "U22") (pin "4") (pinfunction "EN_4") (pintype "passive"))
      (node (ref "U22") (pin "8") (pinfunction "END_8") (pintype "passive"))
      (node (ref "U23") (pin "12") (pinfunction "~{EN}_12") (pintype "passive"))
      (node (ref "U23") (pin "4") (pinfunction "EN_4") (pintype "passive"))
      (node (ref "U23") (pin "8") (pinfunction "END_8") (pintype "passive"))
      (node (ref "U24") (pin "1") (pinfunction "1~{OE}_1") (pintype "passive"))
      (node (ref "U24") (pin "10") (pinfunction "GND_10") (pintype "passive"))
      (node (ref "U24") (pin "19") (pinfunction "2~{OE}_19") (pintype "passive"))
      (node (ref "U25") (pin "1") (pinfunction "1~{OE}_1") (pintype "passive"))
      (node (ref "U25") (pin "10") (pinfunction "GND_10") (pintype "passive"))
      (node (ref "U25") (pin "19") (pinfunction "2~{OE}_19") (pintype "passive"))
      (node (ref "U26") (pin "12") (pinfunction "~{EN}_12") (pintype "passive"))
      (node (ref "U26") (pin "4") (pinfunction "EN_4") (pintype "passive"))
      (node (ref "U26") (pin "8") (pinfunction "END_8") (pintype "passive"))
      (node (ref "U27") (pin "12") (pinfunction "~{EN}_12") (pintype "passive"))
      (node (ref "U27") (pin "4") (pinfunction "EN_4") (pintype "passive"))
      (node (ref "U27") (pin "8") (pinfunction "END_8") (pintype "passive"))
    )
    (net (code "145") (name "Net-(U20A-GFA0{slash}IO207NDB3)") (class "Default")
      (node (ref "R134") (pin "2") (pinfunction "2_2") (pintype "passive"))
      (node (ref "U20") (pin "26") (pinfunction "GFA0/IO207NDB3_26") (pintype "passive"))
    )
    (net (code "146") (name "Net-(U20E-VCCPLF)") (class "Default")
      (node (ref "C132") (pin "1") (pinfunction "1_1") (pintype "passive"))
      (node (ref "C133") (pin "1") (pinfunction "1_1") (pintype "passive"))
      (node (ref "L8") (pin "1") (pinfunction "1_1") (pintype "passive"))
      (node (ref "U20") (pin "27") (pinfunction "VCCPLF_27") (pintype "passive"))
    )
    (net (code "147") (name "Net-(U20E-VCOMPLF)") (class "Default")
      (node (ref "C132") (pin "2") (pinfunction "2_2") (pintype "passive"))
      (node (ref "C133") (pin "2") (pinfunction "2_2") (pintype "passive"))
      (node (ref "L9") (pin "1") (pinfunction "1_1") (pintype "passive"))
      (node (ref "U20") (pin "25") (pinfunction "VCOMPLF_25") (pintype "passive"))
    )
    (net (code "148") (name "Net-(U22-INB)") (class "Default")
      (node (ref "R135") (pin "2") (pinfunction "2_2") (pintype "passive"))
      (node (ref "U22") (pin "7") (pinfunction "INB_7") (pintype "passive"))
    )
    (net (code "149") (name "Net-(U22-IND)") (class "Default")
      (node (ref "R136") (pin "2") (pinfunction "2_2") (pintype "passive"))
      (node (ref "U22") (pin "15") (pinfunction "IND_15") (pintype "passive"))
    )
    (net (code "150") (name "Net-(U24-1A0)") (class "Default")
      (node (ref "R137") (pin "2") (pinfunction "2_2") (pintype "passive"))
      (node (ref "U24") (pin "2") (pinfunction "1A0_2") (pintype "passive"))
    )
    (net (code "151") (name "Net-(U24-1A1)") (class "Default")
      (node (ref "R138") (pin "2") (pinfunction "2_2") (pintype "passive"))
      (node (ref "U24") (pin "4") (pinfunction "1A1_4") (pintype "passive"))
    )
    (net (code "152") (name "Net-(U25-2A0)") (class "Default")
      (node (ref "R139") (pin "1") (pinfunction "1_1") (pintype "passive"))
      (node (ref "U25") (pin "17") (pinfunction "2A0_17") (pintype "passive"))
    )
    (net (code "153") (name "Net-(U25-2A1)") (class "Default")
      (node (ref "R140") (pin "1") (pinfunction "1_1") (pintype "passive"))
      (node (ref "U25") (pin "15") (pinfunction "2A1_15") (pintype "passive"))
    )
    (net (code "154") (name "Net-(U26-INB)") (class "Default")
      (node (ref "R141") (pin "2") (pinfunction "2_2") (pintype "passive"))
      (node (ref "U26") (pin "7") (pinfunction "INB_7") (pintype "passive"))
    )
    (net (code "155") (name "Net-(U26-IND)") (class "Default")
      (node (ref "R143") (pin "2") (pinfunction "2_2") (pintype "passive"))
      (node (ref "U26") (pin "15") (pinfunction "IND_15") (pintype "passive"))
    )
    (net (code "156") (name "Net-(U27-INB)") (class "Default")
      (node (ref "R142") (pin "2") (pinfunction "2_2") (pintype "passive"))
      (node (ref "U27") (pin "7") (pinfunction "INB_7") (pintype "passive"))
    )
    (net (code "157") (name "Net-(U27-IND)") (class "Default")
      (node (ref "R144") (pin "2") (pinfunction "2_2") (pintype "passive"))
      (node (ref "U27") (pin "15") (pinfunction "IND_15") (pintype "passive"))
    )
    (net (code "158") (name "unconnected-(P2-Pad4)") (class "Default")
      (node (ref "P2") (pin "4") (pinfunction "4_4") (pintype "passive+no_connect"))
    )
    (net (code "159") (name "unconnected-(U20A-GEA0{slash}IO188NDB3-Pad49)") (class "Default")
      (node (ref "U20") (pin "49") (pinfunction "GEA0/IO188NDB3_49") (pintype "passive+no_connect"))
    )
    (net (code "160") (name "unconnected-(U20A-GEC0{slash}IO190NDB3-Pad45)") (class "Default")
      (node (ref "U20") (pin "45") (pinfunction "GEC0/IO190NDB3_45") (pintype "passive+no_connect"))
    )
    (net (code "161") (name "unconnected-(U20A-GFA2{slash}IO206PDB3-Pad30)") (class "Default")
      (node (ref "U20") (pin "30") (pinfunction "GFA2/IO206PDB3_30") (pintype "passive+no_connect"))
    )
    (net (code "162") (name "unconnected-(U20A-GFB2{slash}IO205PDB3-Pad32)") (class "Default")
      (node (ref "U20") (pin "32") (pinfunction "GFB2/IO205PDB3_32") (pintype "passive+no_connect"))
    )
    (net (code "163") (name "unconnected-(U20A-IO191NDB3-Pad43)") (class "Default")
      (node (ref "U20") (pin "43") (pinfunction "IO191NDB3_43") (pintype "passive+no_connect"))
    )
    (net (code "164") (name "unconnected-(U20A-IO212NDB3-Pad20)") (class "Default")
      (node (ref "U20") (pin "20") (pinfunction "IO212NDB3_20") (pintype "passive+no_connect"))
    )
    (net (code "165") (name "unconnected-(U20A-IO216PDB3-Pad14)") (class "Default")
      (node (ref "U20") (pin "14") (pinfunction "IO216PDB3_14") (pintype "passive+no_connect"))
    )
    (net (code "166") (name "unconnected-(U20A-IO220PDB3-Pad10)") (class "Default")
      (node (ref "U20") (pin "10") (pinfunction "IO220PDB3_10") (pintype "passive+no_connect"))
    )
    (net (code "167") (name "unconnected-(U20A-IO224NDB3-Pad5)") (class "Default")
      (node (ref "U20") (pin "5") (pinfunction "IO224NDB3_5") (pintype "passive+no_connect"))
    )
    (net (code "168") (name "unconnected-(U20B-GDB2{slash}IO115RSB2-Pad98)") (class "Default")
      (node (ref "U20") (pin "98") (pinfunction "GDB2/IO115RSB2_98") (pintype "passive+no_connect"))
    )
    (net (code "169") (name "unconnected-(U20B-GEB2{slash}IO186RSB2-Pad55)") (class "Default")
      (node (ref "U20") (pin "55") (pinfunction "GEB2/IO186RSB2_55") (pintype "passive+no_connect"))
    )
    (net (code "170") (name "unconnected-(U20B-IO118RSB2-Pad95)") (class "Default")
      (node (ref "U20") (pin "95") (pinfunction "IO118RSB2_95") (pintype "passive+no_connect"))
    )
    (net (code "171") (name "unconnected-(U20B-IO120RSB2-Pad94)") (class "Default")
      (node (ref "U20") (pin "94") (pinfunction "IO120RSB2_94") (pintype "passive+no_connect"))
    )
    (net (code "172") (name "unconnected-(U20B-IO122RSB2-Pad93)") (class "Default")
      (node (ref "U20") (pin "93") (pinfunction "IO122RSB2_93") (pintype "passive+no_connect"))
    )
    (net (code "173") (name "unconnected-(U20B-IO124RSB2-Pad92)") (class "Default")
      (node (ref "U20") (pin "92") (pinfunction "IO124RSB2_92") (pintype "passive+no_connect"))
    )
    (net (code "174") (name "unconnected-(U20B-IO126RSB2-Pad91)") (class "Default")
      (node (ref "U20") (pin "91") (pinfunction "IO126RSB2_91") (pintype "passive+no_connect"))
    )
    (net (code "175") (name "unconnected-(U20B-IO128RSB2-Pad90)") (class "Default")
      (node (ref "U20") (pin "90") (pinfunction "IO128RSB2_90") (pintype "passive+no_connect"))
    )
    (net (code "176") (name "unconnected-(U20B-IO133RSB2-Pad87)") (class "Default")
      (node (ref "U20") (pin "87") (pinfunction "IO133RSB2_87") (pintype "passive+no_connect"))
    )
    (net (code "177") (name "unconnected-(U20B-IO137RSB2-Pad85)") (class "Default")
      (node (ref "U20") (pin "85") (pinfunction "IO137RSB2_85") (pintype "passive+no_connect"))
    )
    (net (code "178") (name "unconnected-(U20B-IO141RSB2-Pad83)") (class "Default")
      (node (ref "U20") (pin "83") (pinfunction "IO141RSB2_83") (pintype "passive+no_connect"))
    )
    (net (code "179") (name "unconnected-(U20B-IO148RSB2-Pad80)") (class "Default")
      (node (ref "U20") (pin "80") (pinfunction "IO148RSB2_80") (pintype "passive+no_connect"))
    )
    (net (code "180") (name "unconnected-(U20B-IO152RSB2-Pad78)") (class "Default")
      (node (ref "U20") (pin "78") (pinfunction "IO152RSB2_78") (pintype "passive+no_connect"))
    )
    (net (code "181") (name "unconnected-(U20B-IO158RSB2-Pad75)") (class "Default")
      (node (ref "U20") (pin "75") (pinfunction "IO158RSB2_75") (pintype "passive+no_connect"))
    )
    (net (code "182") (name "unconnected-(U20B-IO168RSB2-Pad69)") (class "Default")
      (node (ref "U20") (pin "69") (pinfunction "IO168RSB2_69") (pintype "passive+no_connect"))
    )
    (net (code "183") (name "unconnected-(U20B-IO176RSB2-Pad64)") (class "Default")
      (node (ref "U20") (pin "64") (pinfunction "IO176RSB2_64") (pintype "passive+no_connect"))
    )
    (net (code "184") (name "unconnected-(U20B-IO181RSB2-Pad60)") (class "Default")
      (node (ref "U20") (pin "60") (pinfunction "IO181RSB2_60") (pintype "passive+no_connect"))
    )
    (net (code "185") (name "unconnected-(U20B-IO184RSB2-Pad57)") (class "Default")
      (node (ref "U20") (pin "57") (pinfunction "IO184RSB2_57") (pintype "passive+no_connect"))
    )
    (net (code "186") (name "unconnected-(U20C-GCA0{slash}IO93NDB1-Pad133)") (class "Default")
      (node (ref "U20") (pin "133") (pinfunction "GCA0/IO93NDB1_133") (pintype "passive+no_connect"))
    )
    (net (code "187") (name "unconnected-(U20C-GCA2{slash}IO94PSB1-Pad131)") (class "Default")
      (node (ref "U20") (pin "131") (pinfunction "GCA2/IO94PSB1_131") (pintype "passive+no_connect"))
    )
    (net (code "188") (name "unconnected-(U20C-GCB1{slash}IO92PDB1-Pad135)") (class "Default")
      (node (ref "U20") (pin "135") (pinfunction "GCB1/IO92PDB1_135") (pintype "passive+no_connect"))
    )
    (net (code "189") (name "unconnected-(U20C-GCB2{slash}IO95PSB1-Pad129)") (class "Default")
      (node (ref "U20") (pin "129") (pinfunction "GCB2/IO95PSB1_129") (pintype "passive+no_connect"))
    )
    (net (code "190") (name "unconnected-(U20C-GCC2{slash}IO96PDB1-Pad128)") (class "Default")
      (node (ref "U20") (pin "128") (pinfunction "GCC2/IO96PDB1_128") (pintype "passive+no_connect"))
    )
    (net (code "191") (name "unconnected-(U20C-GDB1{slash}IO112PDB1-Pad114)") (class "Default")
      (node (ref "U20") (pin "114") (pinfunction "GDB1/IO112PDB1_114") (pintype "passive+no_connect"))
    )
    (net (code "192") (name "unconnected-(U20C-IO79NDB1-Pad150)") (class "Default")
      (node (ref "U20") (pin "150") (pinfunction "IO79NDB1_150") (pintype "passive+no_connect"))
    )
    (net (code "193") (name "unconnected-(U20C-IO82NDB1-Pad146)") (class "Default")
      (node (ref "U20") (pin "146") (pinfunction "IO82NDB1_146") (pintype "passive+no_connect"))
    )
    (net (code "194") (name "unconnected-(U20C-IO88PDB1-Pad139)") (class "Default")
      (node (ref "U20") (pin "139") (pinfunction "IO88PDB1_139") (pintype "passive+no_connect"))
    )
    (net (code "195") (name "unconnected-(U20C-IO109PDB1-Pad118)") (class "Default")
      (node (ref "U20") (pin "118") (pinfunction "IO109PDB1_118") (pintype "passive+no_connect"))
    )
    (net (code "196") (name "unconnected-(U20D-GAB0{slash}IO02RSB0-Pad204)") (class "Default")
      (node (ref "U20") (pin "204") (pinfunction "GAB0/IO02RSB0_204") (pintype "passive+no_connect"))
    )
    (net (code "197") (name "unconnected-(U20D-GBA0{slash}IO76RSB0-Pad159)") (class "Default")
      (node (ref "U20") (pin "159") (pinfunction "GBA0/IO76RSB0_159") (pintype "passive+no_connect"))
    )
    (net (code "198") (name "unconnected-(U20D-GBA1{slash}IO77RSB0-Pad158)") (class "Default")
      (node (ref "U20") (pin "158") (pinfunction "GBA1/IO77RSB0_158") (pintype "passive+no_connect"))
    )
    (net (code "199") (name "unconnected-(U20D-GBB0{slash}IO74RSB0-Pad161)") (class "Default")
      (node (ref "U20") (pin "161") (pinfunction "GBB0/IO74RSB0_161") (pintype "passive+no_connect"))
    )
    (net (code "200") (name "unconnected-(U20D-GBC0{slash}IO72RSB0-Pad164)") (class "Default")
      (node (ref "U20") (pin "164") (pinfunction "GBC0/IO72RSB0_164") (pintype "passive+no_connect"))
    )
    (net (code "201") (name "unconnected-(U20D-IO12RSB0-Pad196)") (class "Default")
      (node (ref "U20") (pin "196") (pinfunction "IO12RSB0_196") (pintype "passive+no_connect"))
    )
    (net (code "202") (name "unconnected-(U20D-IO14RSB0-Pad193)") (class "Default")
      (node (ref "U20") (pin "193") (pinfunction "IO14RSB0_193") (pintype "passive+no_connect"))
    )
    (net (code "203") (name "unconnected-(U20D-IO15RSB0-Pad192)") (class "Default")
      (node (ref "U20") (pin "192") (pinfunction "IO15RSB0_192") (pintype "passive+no_connect"))
    )
    (net (code "204") (name "unconnected-(U20D-IO16RSB0-Pad191)") (class "Default")
      (node (ref "U20") (pin "191") (pinfunction "IO16RSB0_191") (pintype "passive+no_connect"))
    )
    (net (code "205") (name "unconnected-(U20D-IO18RSB0-Pad190)") (class "Default")
      (node (ref "U20") (pin "190") (pinfunction "IO18RSB0_190") (pintype "passive+no_connect"))
    )
    (net (code "206") (name "unconnected-(U20D-IO27RSB0-Pad184)") (class "Default")
      (node (ref "U20") (pin "184") (pinfunction "IO27RSB0_184") (pintype "passive+no_connect"))
    )
    (net (code "207") (name "unconnected-(U20D-IO31RSB0-Pad182)") (class "Default")
      (node (ref "U20") (pin "182") (pinfunction "IO31RSB0_182") (pintype "passive+no_connect"))
    )
    (net (code "208") (name "unconnected-(U20D-IO35RSB0-Pad180)") (class "Default")
      (node (ref "U20") (pin "180") (pinfunction "IO35RSB0_180") (pintype "passive+no_connect"))
    )
    (net (code "209") (name "unconnected-(U20D-IO40RSB0-Pad177)") (class "Default")
      (node (ref "U20") (pin "177") (pinfunction "IO40RSB0_177") (pintype "passive+no_connect"))
    )
    (net (code "210") (name "unconnected-(U20D-IO45RSB0-Pad175)") (class "Default")
      (node (ref "U20") (pin "175") (pinfunction "IO45RSB0_175") (pintype "passive+no_connect"))
    )
    (net (code "211") (name "unconnected-(U20D-IO51RSB0-Pad173)") (class "Default")
      (node (ref "U20") (pin "173") (pinfunction "IO51RSB0_173") (pintype "passive+no_connect"))
    )
    (net (code "212") (name "unconnected-(U20D-IO60RSB0-Pad168)") (class "Default")
      (node (ref "U20") (pin "168") (pinfunction "IO60RSB0_168") (pintype "passive+no_connect"))
    )
    (net (code "213") (name "unconnected-(U20D-IO67RSB0-Pad166)") (class "Default")
      (node (ref "U20") (pin "166") (pinfunction "IO67RSB0_166") (pintype "passive+no_connect"))
    )
    (net (code "214") (name "unconnected-(U20F-NC-Pad126)") (class "Default")
      (node (ref "U20") (pin "126") (pinfunction "NC_126") (pintype "passive+no_connect"))
    )
    (net (code "215") (name "unconnected-(U21-NC-Pad1)") (class "Default")
      (node (ref "U21") (pin "1") (pinfunction "NC_1") (pintype "passive+no_connect"))
    )
    (net (code "216") (name "unconnected-(U22-OUTB_N-Pad5)") (class "Default")
      (node (ref "U22") (pin "5") (pinfunction "OUTB_N_5") (pintype "passive+no_connect"))
    )
    (net (code "217") (name "unconnected-(U22-OUTB_P-Pad6)") (class "Default")
      (node (ref "U22") (pin "6") (pinfunction "OUTB_P_6") (pintype "passive+no_connect"))
    )
    (net (code "218") (name "unconnected-(U22-OUTD_N-Pad13)") (class "Default")
      (node (ref "U22") (pin "13") (pinfunction "OUTD_N_13") (pintype "passive+no_connect"))
    )
    (net (code "219") (name "unconnected-(U22-OUTD_P-Pad14)") (class "Default")
      (node (ref "U22") (pin "14") (pinfunction "OUTD_P_14") (pintype "passive+no_connect"))
    )
    (net (code "220") (name "unconnected-(U24-1Y0-Pad18)") (class "Default")
      (node (ref "U24") (pin "18") (pinfunction "1Y0_18") (pintype "passive+no_connect"))
    )
    (net (code "221") (name "unconnected-(U24-1Y1-Pad16)") (class "Default")
      (node (ref "U24") (pin "16") (pinfunction "1Y1_16") (pintype "passive+no_connect"))
    )
    (net (code "222") (name "unconnected-(U25-2Y0-Pad3)") (class "Default")
      (node (ref "U25") (pin "3") (pinfunction "2Y0_3") (pintype "passive+no_connect"))
    )
    (net (code "223") (name "unconnected-(U25-2Y1-Pad5)") (class "Default")
      (node (ref "U25") (pin "5") (pinfunction "2Y1_5") (pintype "passive+no_connect"))
    )
    (net (code "224") (name "unconnected-(U26-OUTB_N-Pad5)") (class "Default")
      (node (ref "U26") (pin "5") (pinfunction "OUTB_N_5") (pintype "passive+no_connect"))
    )
    (net (code "225") (name "unconnected-(U26-OUTB_P-Pad6)") (class "Default")
      (node (ref "U26") (pin "6") (pinfunction "OUTB_P_6") (pintype "passive+no_connect"))
    )
    (net (code "226") (name "unconnected-(U26-OUTD_N-Pad13)") (class "Default")
      (node (ref "U26") (pin "13") (pinfunction "OUTD_N_13") (pintype "passive+no_connect"))
    )
    (net (code "227") (name "unconnected-(U26-OUTD_P-Pad14)") (class "Default")
      (node (ref "U26") (pin "14") (pinfunction "OUTD_P_14") (pintype "passive+no_connect"))
    )
    (net (code "228") (name "unconnected-(U27-OUTB_N-Pad5)") (class "Default")
      (node (ref "U27") (pin "5") (pinfunction "OUTB_N_5") (pintype "passive+no_connect"))
    )
    (net (code "229") (name "unconnected-(U27-OUTB_P-Pad6)") (class "Default")
      (node (ref "U27") (pin "6") (pinfunction "OUTB_P_6") (pintype "passive+no_connect"))
    )
    (net (code "230") (name "unconnected-(U27-OUTD_N-Pad13)") (class "Default")
      (node (ref "U27") (pin "13") (pinfunction "OUTD_N_13") (pintype "passive+no_connect"))
    )
    (net (code "231") (name "unconnected-(U27-OUTD_P-Pad14)") (class "Default")
      (node (ref "U27") (pin "14") (pinfunction "OUTD_P_14") (pintype "passive+no_connect"))
    )
  )
)
